# odbiornik2.net
KiCad netlist of a schematic drawn in EAGLE
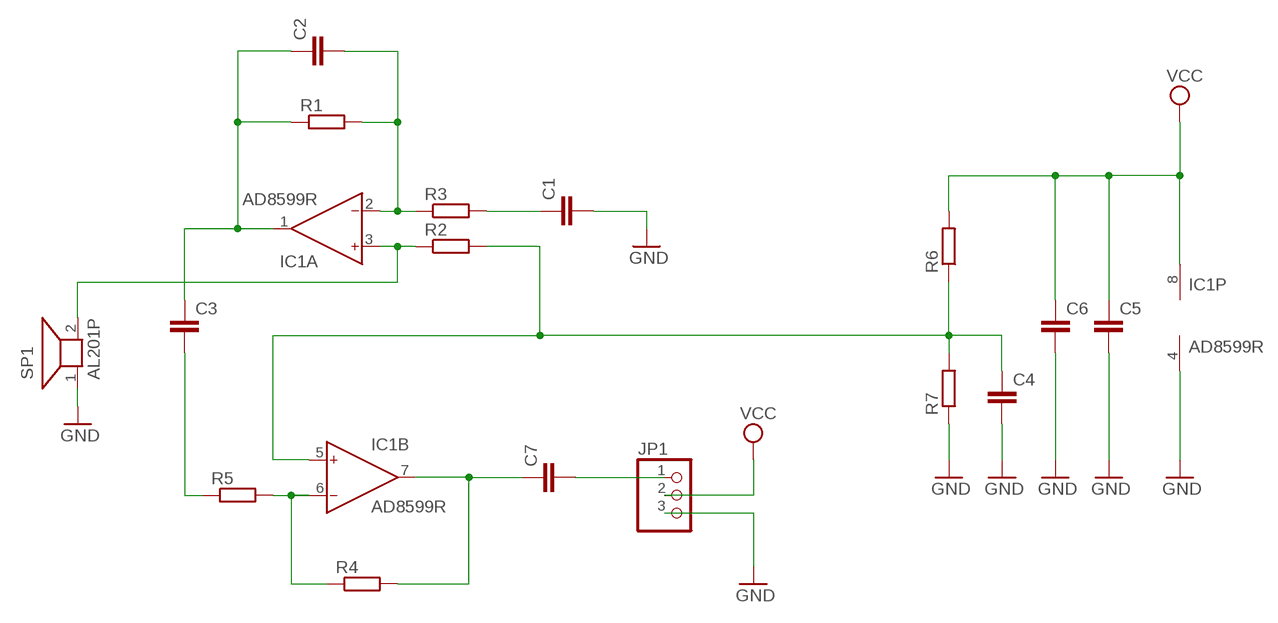
[diagram p0: schematic, sheet 1]

(export (version "E")
  (design (tool "Eeschema 10.0.6"))
  (components
    (comp (ref "C1")
      (value "C-EUC1206K")
      (footprint "eagle-import:C1206K")
      (libsource (lib "eagle-import") (part "C-EUC1206K"))
    )
    (comp (ref "C2")
      (value "C-EUC1206K")
      (footprint "eagle-import:C1206K")
      (libsource (lib "eagle-import") (part "C-EUC1206K"))
    )
    (comp (ref "C3")
      (value "C-EUC1206K")
      (footprint "eagle-import:C1206K")
      (libsource (lib "eagle-import") (part "C-EUC1206K"))
    )
    (comp (ref "C4")
      (value "C-EUC1206K")
      (footprint "eagle-import:C1206K")
      (libsource (lib "eagle-import") (part "C-EUC1206K"))
    )
    (comp (ref "C5")
      (value "C-EUC1206K")
      (footprint "eagle-import:C1206K")
      (libsource (lib "eagle-import") (part "C-EUC1206K"))
    )
    (comp (ref "C6")
      (value "C-EUC1206")
      (footprint "eagle-import:C1206")
      (libsource (lib "eagle-import") (part "C-EUC1206"))
    )
    (comp (ref "C7")
      (value "C-EUC1206")
      (footprint "eagle-import:C1206")
      (libsource (lib "eagle-import") (part "C-EUC1206"))
    )
    (comp (ref "IC1")
      (value "AD8599R")
      (footprint "eagle-import:SO8")
      (fields (field (name "MPN") "AD8599ARZ"))
      (libsource (lib "eagle-import") (part "AD8599R"))
    )
    (comp (ref "JP1")
      (value "PINHD-1X3")
      (footprint "eagle-import:1X03")
      (libsource (lib "eagle-import") (part "PINHD-1X3"))
    )
    (comp (ref "R1")
      (value "R-EU_R0805")
      (footprint "eagle-import:R0805")
      (libsource (lib "eagle-import") (part "R-EU_R0805"))
    )
    (comp (ref "R2")
      (value "R-EU_R0805")
      (footprint "eagle-import:R0805")
      (libsource (lib "eagle-import") (part "R-EU_R0805"))
    )
    (comp (ref "R3")
      (value "R-EU_R0805")
      (footprint "eagle-import:R0805")
      (libsource (lib "eagle-import") (part "R-EU_R0805"))
    )
    (comp (ref "R4")
      (value "R-EU_R0805")
      (footprint "eagle-import:R0805")
      (libsource (lib "eagle-import") (part "R-EU_R0805"))
    )
    (comp (ref "R5")
      (value "R-EU_R0805")
      (footprint "eagle-import:R0805")
      (libsource (lib "eagle-import") (part "R-EU_R0805"))
    )
    (comp (ref "R6")
      (value "R-EU_R0805")
      (footprint "eagle-import:R0805")
      (libsource (lib "eagle-import") (part "R-EU_R0805"))
    )
    (comp (ref "R7")
      (value "R-EU_R0805")
      (footprint "eagle-import:R0805")
      (libsource (lib "eagle-import") (part "R-EU_R0805"))
    )
    (comp (ref "SP1")
      (value "AL201P")
      (footprint "eagle-import:AL201P")
      (libsource (lib "eagle-import") (part "AL201P"))
    )
  )
  (nets
    (net (code "1") (name "GND") (class "Default")
      (node (ref "C1") (pin "2") (pinfunction "2_2") (pintype "passive"))
      (node (ref "C4") (pin "2") (pinfunction "2_2") (pintype "passive"))
      (node (ref "C5") (pin "2") (pinfunction "2_2") (pintype "passive"))
      (node (ref "C6") (pin "2") (pinfunction "2_2") (pintype "passive"))
      (node (ref "IC1") (pin "4") (pinfunction "V-_4") (pintype "power_in"))
      (node (ref "JP1") (pin "3") (pinfunction "3_3") (pintype "passive"))
      (node (ref "R7") (pin "1") (pinfunction "1_1") (pintype "passive"))
      (node (ref "SP1") (pin "1") (pinfunction "1_1") (pintype "passive"))
    )
    (net (code "2") (name "Net-(C1-Pad1)") (class "Default")
      (node (ref "C1") (pin "1") (pinfunction "1_1") (pintype "passive"))
      (node (ref "R3") (pin "2") (pinfunction "2_2") (pintype "passive"))
    )
    (net (code "3") (name "Net-(C3-Pad2)") (class "Default")
      (node (ref "C3") (pin "2") (pinfunction "2_2") (pintype "passive"))
      (node (ref "R5") (pin "1") (pinfunction "1_1") (pintype "passive"))
    )
    (net (code "4") (name "Net-(C7-Pad2)") (class "Default")
      (node (ref "C7") (pin "2") (pinfunction "2_2") (pintype "passive"))
      (node (ref "JP1") (pin "1") (pinfunction "1_1") (pintype "passive"))
    )
    (net (code "5") (name "Net-(IC1A-IN+)") (class "Default")
      (node (ref "IC1") (pin "3") (pinfunction "IN+_3") (pintype "input"))
      (node (ref "R2") (pin "1") (pinfunction "1_1") (pintype "passive"))
      (node (ref "SP1") (pin "2") (pinfunction "2_2") (pintype "passive"))
    )
    (net (code "6") (name "Net-(IC1A-IN-)") (class "Default")
      (node (ref "C2") (pin "2") (pinfunction "2_2") (pintype "passive"))
      (node (ref "IC1") (pin "2") (pinfunction "IN-_2") (pintype "input"))
      (node (ref "R1") (pin "2") (pinfunction "2_2") (pintype "passive"))
      (node (ref "R3") (pin "1") (pinfunction "1_1") (pintype "passive"))
    )
    (net (code "7") (name "Net-(IC1A-OUT)") (class "Default")
      (node (ref "C2") (pin "1") (pinfunction "1_1") (pintype "passive"))
      (node (ref "C3") (pin "1") (pinfunction "1_1") (pintype "passive"))
      (node (ref "IC1") (pin "1") (pinfunction "OUT_1") (pintype "output"))
      (node (ref "R1") (pin "1") (pinfunction "1_1") (pintype "passive"))
    )
    (net (code "8") (name "Net-(IC1B-IN+)") (class "Default")
      (node (ref "C4") (pin "1") (pinfunction "1_1") (pintype "passive"))
      (node (ref "IC1") (pin "5") (pinfunction "IN+_5") (pintype "input"))
      (node (ref "R2") (pin "2") (pinfunction "2_2") (pintype "passive"))
      (node (ref "R6") (pin "1") (pinfunction "1_1") (pintype "passive"))
      (node (ref "R7") (pin "2") (pinfunction "2_2") (pintype "passive"))
    )
    (net (code "9") (name "Net-(IC1B-IN-)") (class "Default")
      (node (ref "IC1") (pin "6") (pinfunction "IN-_6") (pintype "input"))
      (node (ref "R4") (pin "1") (pinfunction "1_1") (pintype "passive"))
      (node (ref "R5") (pin "2") (pinfunction "2_2") (pintype "passive"))
    )
    (net (code "10") (name "Net-(IC1B-OUT)") (class "Default")
      (node (ref "C7") (pin "1") (pinfunction "1_1") (pintype "passive"))
      (node (ref "IC1") (pin "7") (pinfunction "OUT_7") (pintype "output"))
      (node (ref "R4") (pin "2") (pinfunction "2_2") (pintype "passive"))
    )
    (net (code "11") (name "VCC") (class "Default")
      (node (ref "C5") (pin "1") (pinfunction "1_1") (pintype "passive"))
      (node (ref "C6") (pin "1") (pinfunction "1_1") (pintype "passive"))
      (node (ref "IC1") (pin "8") (pinfunction "V+_8") (pintype "power_in"))
      (node (ref "JP1") (pin "2") (pinfunction "2_2") (pintype "passive"))
      (node (ref "R6") (pin "2") (pinfunction "2_2") (pintype "passive"))
    )
  )
)
